# MCU-144pins.net
KiCad netlist of a schematic drawn in Altium Designer
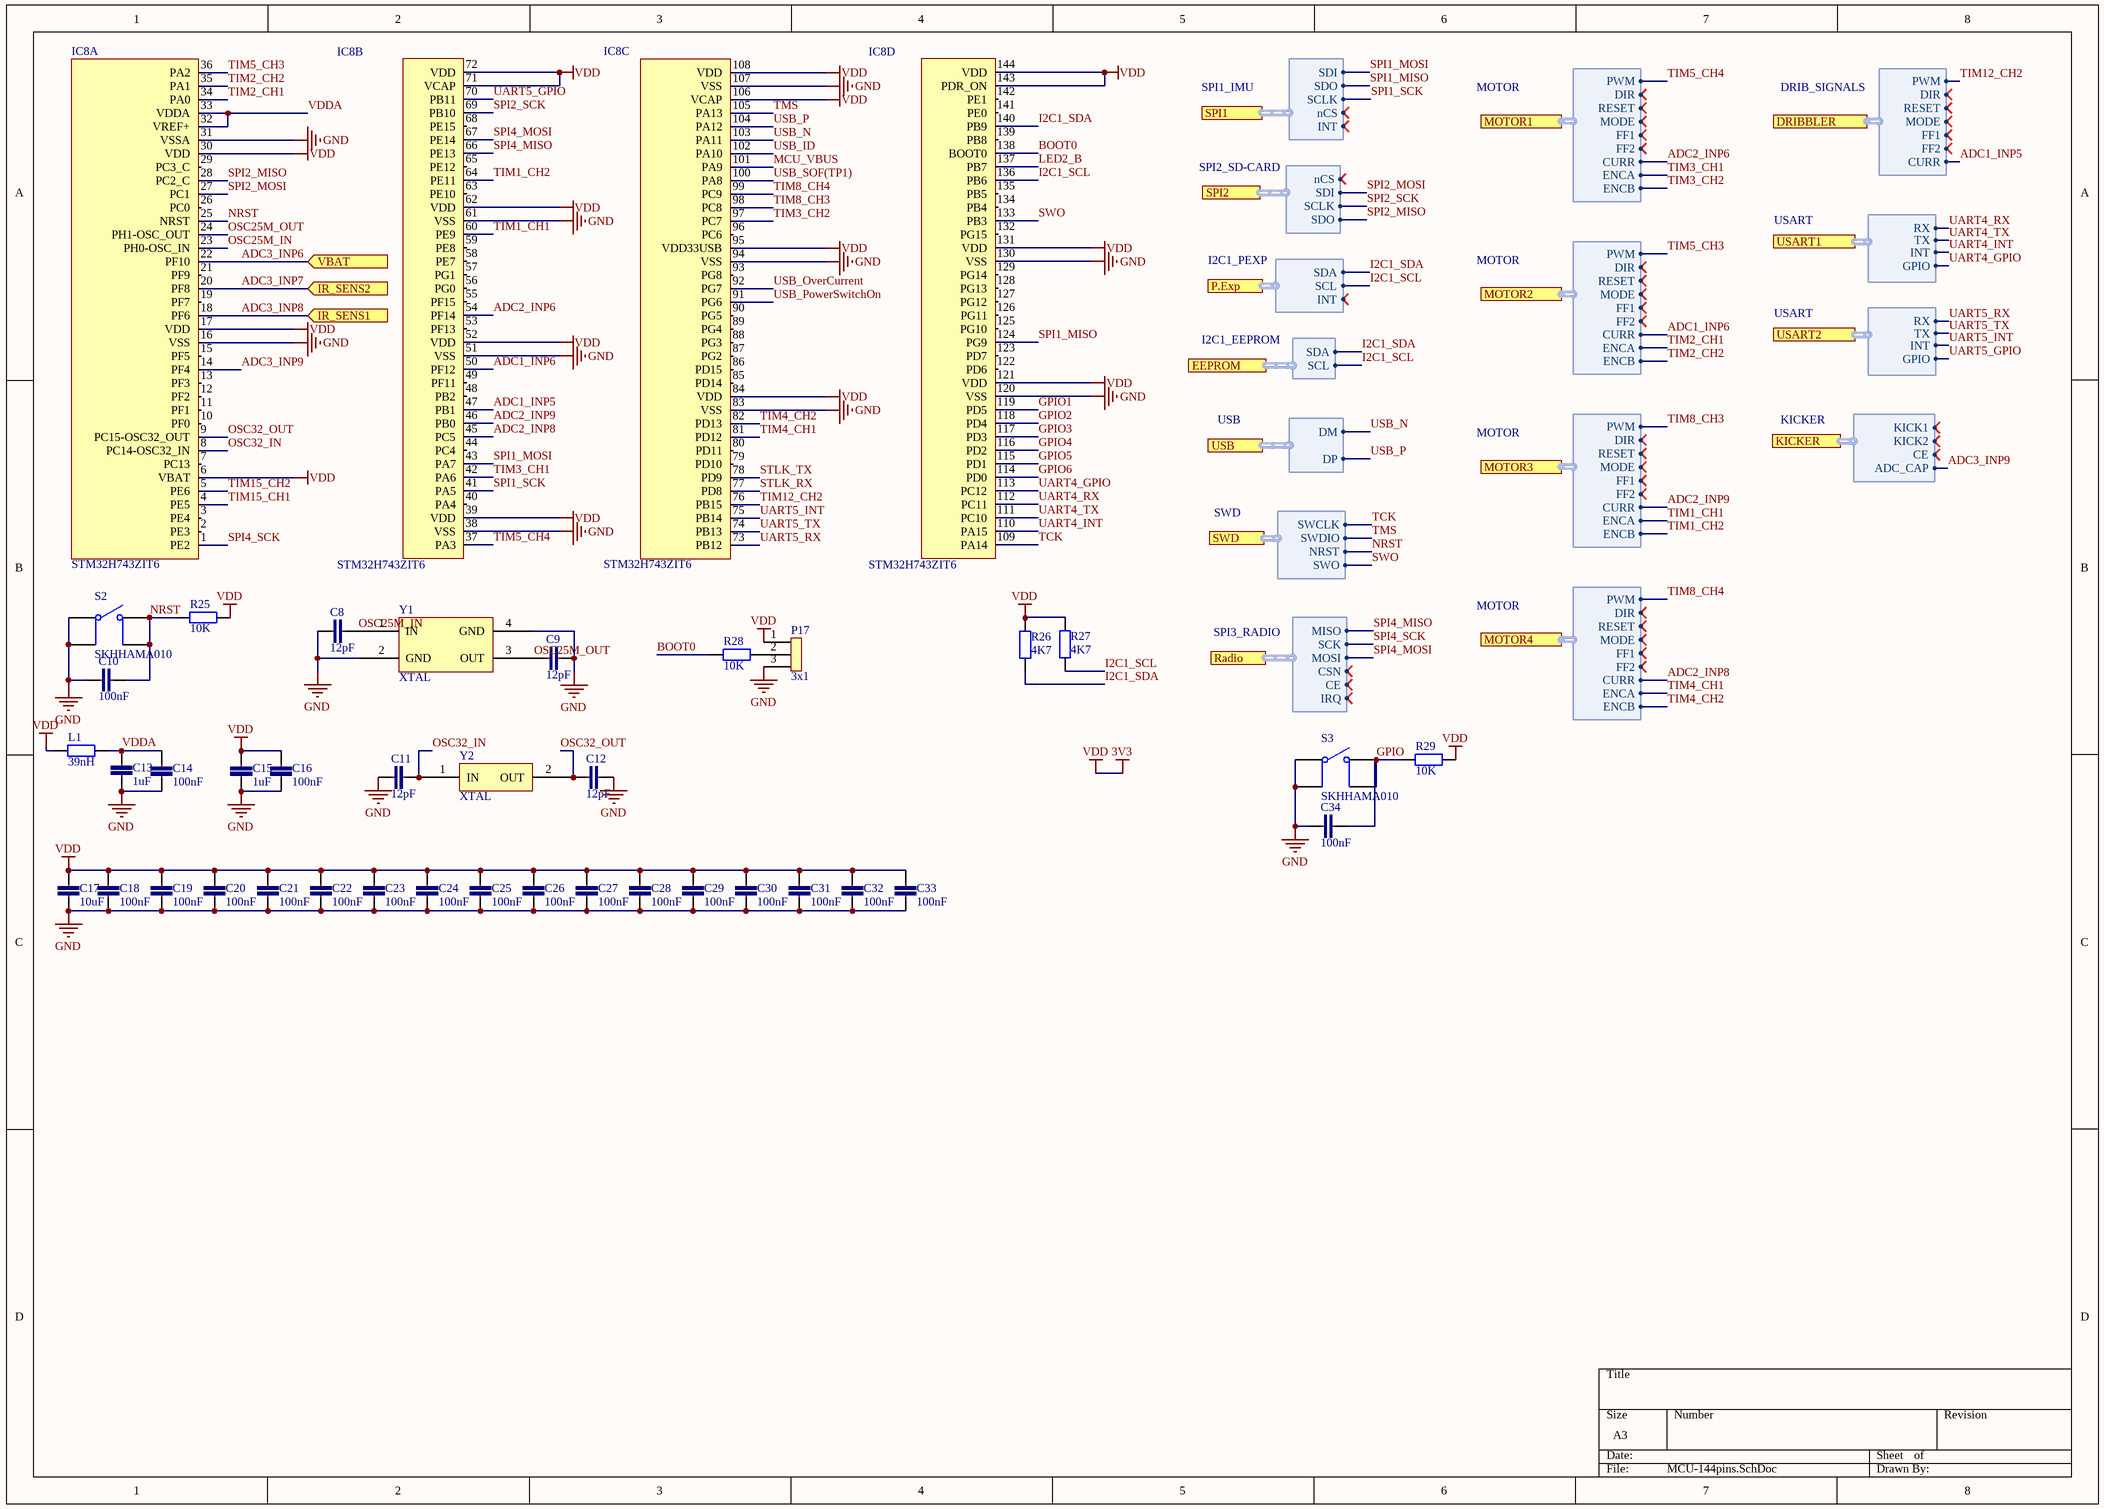
[diagram p0: MCU-144pins.SchDoc]

(export (version "E")
  (design (tool "Eeschema 10.0.6"))
  (components
    (comp (ref "C8")
      (value "12pF")
      (footprint "CAP CER 0603")
      (description "Multilayer Ceramic Capacitors MLCC - SMD/SMT 50V 12pF 0603 C0G 5%")
      (fields (field (name "MFR") "KEMET"))
      (libsource (lib "SSL-2020-SchLib1") (part "CAP CER 0603 50V 12pF"))
    )
    (comp (ref "C9")
      (value "12pF")
      (footprint "CAP CER 0603")
      (description "Multilayer Ceramic Capacitors MLCC - SMD/SMT 50V 12pF 0603 C0G 5%")
      (fields (field (name "MFR") "KEMET"))
      (libsource (lib "SSL-2020-SchLib1") (part "CAP CER 0603 50V 12pF"))
    )
    (comp (ref "C10")
      (value "100nF")
      (footprint "CAP CER 0603")
      (description "Multilayer Ceramic Capacitors MLCC - SMD/SMT 25V 0.1uF 0603 Y5V -20/+80%")
      (fields (field (name "MFR") "KEMET"))
      (libsource (lib "") (part "CAP CER 0603 25V 100nF_1"))
    )
    (comp (ref "C11")
      (value "12pF")
      (footprint "CAP CER 0603")
      (description "Multilayer Ceramic Capacitors MLCC - SMD/SMT 50V 12pF 0603 C0G 5%")
      (fields (field (name "MFR") "KEMET"))
      (libsource (lib "SSL-2020-SchLib1") (part "CAP CER 0603 50V 12pF"))
    )
    (comp (ref "C12")
      (value "12pF")
      (footprint "CAP CER 0603")
      (description "Multilayer Ceramic Capacitors MLCC - SMD/SMT 50V 12pF 0603 C0G 5%")
      (fields (field (name "MFR") "KEMET"))
      (libsource (lib "SSL-2020-SchLib1") (part "CAP CER 0603 50V 12pF"))
    )
    (comp (ref "C13")
      (value "1uF")
      (footprint "CAP CER 0603")
      (description "Multilayer Ceramic Capacitors MLCC - SMD/SMT 1uF 25V X5R 10%")
      (fields (field (name "MFR") "KEMET"))
      (libsource (lib "SSL-2020-SchLib1") (part "CAP CER 0603 25V 1uF"))
    )
    (comp (ref "C14")
      (value "100nF")
      (footprint "CAP CER 0603")
      (description "Multilayer Ceramic Capacitors MLCC - SMD/SMT 25V 0.1uF 0603 Y5V -20/+80%")
      (fields (field (name "MFR") "KEMET"))
      (libsource (lib "SSL-2020-SchLib1") (part "CAP CER 0603 25V 100nF"))
    )
    (comp (ref "C15")
      (value "1uF")
      (footprint "CAP CER 0603")
      (description "Multilayer Ceramic Capacitors MLCC - SMD/SMT 1uF 25V X5R 10%")
      (fields (field (name "MFR") "KEMET"))
      (libsource (lib "SSL-2020-SchLib1") (part "CAP CER 0603 25V 1uF"))
    )
    (comp (ref "C16")
      (value "100nF")
      (footprint "CAP CER 0603")
      (description "Multilayer Ceramic Capacitors MLCC - SMD/SMT 25V 0.1uF 0603 Y5V -20/+80%")
      (fields (field (name "MFR") "KEMET"))
      (libsource (lib "SSL-2020-SchLib1") (part "CAP CER 0603 25V 100nF"))
    )
    (comp (ref "C17")
      (value "10uF")
      (footprint "CAP CER 0603")
      (description "Multilayer Ceramic Capacitors MLCC - SMD/SMT 0603 6.3V 10uF X5R 10% Soft Term")
      (fields (field (name "MFR") "TDK"))
      (libsource (lib "SSL-2020-SchLib1") (part "CAP CER 0603 6.3V 10uF"))
    )
    (comp (ref "C18")
      (value "100nF")
      (footprint "CAP CER 0603")
      (description "Multilayer Ceramic Capacitors MLCC - SMD/SMT 25V 0.1uF 0603 Y5V -20/+80%")
      (fields (field (name "MFR") "KEMET"))
      (libsource (lib "SSL-2020-SchLib1") (part "CAP CER 0603 25V 100nF"))
    )
    (comp (ref "C19")
      (value "100nF")
      (footprint "CAP CER 0603")
      (description "Multilayer Ceramic Capacitors MLCC - SMD/SMT 25V 0.1uF 0603 Y5V -20/+80%")
      (fields (field (name "MFR") "KEMET"))
      (libsource (lib "SSL-2020-SchLib1") (part "CAP CER 0603 25V 100nF"))
    )
    (comp (ref "C20")
      (value "100nF")
      (footprint "CAP CER 0603")
      (description "Multilayer Ceramic Capacitors MLCC - SMD/SMT 25V 0.1uF 0603 Y5V -20/+80%")
      (fields (field (name "MFR") "KEMET"))
      (libsource (lib "SSL-2020-SchLib1") (part "CAP CER 0603 25V 100nF"))
    )
    (comp (ref "C21")
      (value "100nF")
      (footprint "CAP CER 0603")
      (description "Multilayer Ceramic Capacitors MLCC - SMD/SMT 25V 0.1uF 0603 Y5V -20/+80%")
      (fields (field (name "MFR") "KEMET"))
      (libsource (lib "SSL-2020-SchLib1") (part "CAP CER 0603 25V 100nF"))
    )
    (comp (ref "C22")
      (value "100nF")
      (footprint "CAP CER 0603")
      (description "Multilayer Ceramic Capacitors MLCC - SMD/SMT 25V 0.1uF 0603 Y5V -20/+80%")
      (fields (field (name "MFR") "KEMET"))
      (libsource (lib "SSL-2020-SchLib1") (part "CAP CER 0603 25V 100nF"))
    )
    (comp (ref "C23")
      (value "100nF")
      (footprint "CAP CER 0603")
      (description "Multilayer Ceramic Capacitors MLCC - SMD/SMT 25V 0.1uF 0603 Y5V -20/+80%")
      (fields (field (name "MFR") "KEMET"))
      (libsource (lib "SSL-2020-SchLib1") (part "CAP CER 0603 25V 100nF"))
    )
    (comp (ref "C24")
      (value "100nF")
      (footprint "CAP CER 0603")
      (description "Multilayer Ceramic Capacitors MLCC - SMD/SMT 25V 0.1uF 0603 Y5V -20/+80%")
      (fields (field (name "MFR") "KEMET"))
      (libsource (lib "SSL-2020-SchLib1") (part "CAP CER 0603 25V 100nF"))
    )
    (comp (ref "C25")
      (value "100nF")
      (footprint "CAP CER 0603")
      (description "Multilayer Ceramic Capacitors MLCC - SMD/SMT 25V 0.1uF 0603 Y5V -20/+80%")
      (fields (field (name "MFR") "KEMET"))
      (libsource (lib "SSL-2020-SchLib1") (part "CAP CER 0603 25V 100nF"))
    )
    (comp (ref "C26")
      (value "100nF")
      (footprint "CAP CER 0603")
      (description "Multilayer Ceramic Capacitors MLCC - SMD/SMT 25V 0.1uF 0603 Y5V -20/+80%")
      (fields (field (name "MFR") "KEMET"))
      (libsource (lib "SSL-2020-SchLib1") (part "CAP CER 0603 25V 100nF"))
    )
    (comp (ref "C27")
      (value "100nF")
      (footprint "CAP CER 0603")
      (description "Multilayer Ceramic Capacitors MLCC - SMD/SMT 25V 0.1uF 0603 Y5V -20/+80%")
      (fields (field (name "MFR") "KEMET"))
      (libsource (lib "SSL-2020-SchLib1") (part "CAP CER 0603 25V 100nF"))
    )
    (comp (ref "C28")
      (value "100nF")
      (footprint "CAP CER 0603")
      (description "Multilayer Ceramic Capacitors MLCC - SMD/SMT 25V 0.1uF 0603 Y5V -20/+80%")
      (fields (field (name "MFR") "KEMET"))
      (libsource (lib "SSL-2020-SchLib1") (part "CAP CER 0603 25V 100nF"))
    )
    (comp (ref "C29")
      (value "100nF")
      (footprint "CAP CER 0603")
      (description "Multilayer Ceramic Capacitors MLCC - SMD/SMT 25V 0.1uF 0603 Y5V -20/+80%")
      (fields (field (name "MFR") "KEMET"))
      (libsource (lib "SSL-2020-SchLib1") (part "CAP CER 0603 25V 100nF"))
    )
    (comp (ref "C30")
      (value "100nF")
      (footprint "CAP CER 0603")
      (description "Multilayer Ceramic Capacitors MLCC - SMD/SMT 25V 0.1uF 0603 Y5V -20/+80%")
      (fields (field (name "MFR") "KEMET"))
      (libsource (lib "SSL-2020-SchLib1") (part "CAP CER 0603 25V 100nF"))
    )
    (comp (ref "C31")
      (value "100nF")
      (footprint "CAP CER 0603")
      (description "Multilayer Ceramic Capacitors MLCC - SMD/SMT 25V 0.1uF 0603 Y5V -20/+80%")
      (fields (field (name "MFR") "KEMET"))
      (libsource (lib "SSL-2020-SchLib1") (part "CAP CER 0603 25V 100nF"))
    )
    (comp (ref "C32")
      (value "100nF")
      (footprint "CAP CER 0603")
      (description "Multilayer Ceramic Capacitors MLCC - SMD/SMT 25V 0.1uF 0603 Y5V -20/+80%")
      (fields (field (name "MFR") "KEMET"))
      (libsource (lib "SSL-2020-SchLib1") (part "CAP CER 0603 25V 100nF"))
    )
    (comp (ref "C33")
      (value "100nF")
      (footprint "CAP CER 0603")
      (description "Multilayer Ceramic Capacitors MLCC - SMD/SMT 25V 0.1uF 0603 Y5V -20/+80%")
      (fields (field (name "MFR") "KEMET"))
      (libsource (lib "SSL-2020-SchLib1") (part "CAP CER 0603 25V 100nF"))
    )
    (comp (ref "C34")
      (value "100nF")
      (footprint "CAP CER 0603")
      (description "Multilayer Ceramic Capacitors MLCC - SMD/SMT 25V 0.1uF 0603 Y5V -20/+80%")
      (fields (field (name "MFR") "KEMET"))
      (libsource (lib "") (part "CAP CER 0603 25V 100nF_1"))
    )
    (comp (ref "IC8")
      (value "STM32H743ZIT6")
      (footprint "LQFP-144")
      (fields (field (name "MFR") "STMicroelectronics"))
      (libsource (lib "SSL-2020-SchLib1") (part "STM32H743ZIT6"))
    )
    (comp (ref "L1")
      (value "39nH")
      (footprint "IND SMD 0603")
      (description "FIXED IND 39NH 300MA 600 MOHM")
      (libsource (lib "SSL-2020-SchLib1") (part "IND SMD 0603 300mA"))
    )
    (comp (ref "P17")
      (value "3x1")
      (footprint "HEADER 3X1 MALE")
      (description "Headers & Wire Housings 03 SIL VERTICAL PIN HEADER TIN")
      (libsource (lib "SSL-2020-SchLib1") (part "HEADER 3P M"))
    )
    (comp (ref "R25")
      (value "10K")
      (footprint "RES SMD 0603")
      (description "Thick Film Resistors - SMD 1/10Watt 10Kohms 1% Commercial Use")
      (fields (field (name "MFR") "Vishay / Dale"))
      (libsource (lib "SSL-2020-SchLib1") (part "RES SMD 0603 10K"))
    )
    (comp (ref "R26")
      (value "4K7")
      (footprint "RES SMD 0603")
      (libsource (lib "SSL-2020-SchLib1") (part "RES SMD 0603 4K7"))
    )
    (comp (ref "R27")
      (value "4K7")
      (footprint "RES SMD 0603")
      (libsource (lib "SSL-2020-SchLib1") (part "RES SMD 0603 4K7"))
    )
    (comp (ref "R28")
      (value "10K")
      (footprint "RES SMD 0603")
      (description "Thick Film Resistors - SMD 1/10Watt 10Kohms 1% Commercial Use")
      (fields (field (name "MFR") "Vishay / Dale"))
      (libsource (lib "SSL-2020-SchLib1") (part "RES SMD 0603 10K"))
    )
    (comp (ref "R29")
      (value "10K")
      (footprint "RES SMD 0603")
      (description "Thick Film Resistors - SMD 1/10Watt 10Kohms 1% Commercial Use")
      (fields (field (name "MFR") "Vishay / Dale"))
      (libsource (lib "SSL-2020-SchLib1") (part "RES SMD 0603 10K"))
    )
    (comp (ref "S2")
      (value "SKHHAMA010")
      (footprint "TACT-SWITCH-6X6X5")
      (description "Tactile Switches 6.0x6.0x5.0mm 160gf")
      (fields (field (name "MFR") "ALPS"))
      (libsource (lib "SSL-2020-SchLib1") (part "SKHHAMA010"))
    )
    (comp (ref "S3")
      (value "SKHHAMA010")
      (footprint "TACT-SWITCH-6X6X5")
      (description "Tactile Switches 6.0x6.0x5.0mm 160gf")
      (fields (field (name "MFR") "ALPS"))
      (libsource (lib "SSL-2020-SchLib1") (part "SKHHAMA010"))
    )
    (comp (ref "Y1")
      (value "XTAL")
      (footprint "XTAL-200X160")
      (description "Crystals 25MHz 10PPM -20C +75C 9.0pF")
      (fields (field (name "MFR") "Epson Timing") (field (name "TOLERANCE") "10 PPM"))
      (libsource (lib "SSL-2020-SchLib1") (part "FA-12825F10Z-AC"))
    )
    (comp (ref "Y2")
      (value "XTAL")
      (footprint "XTAL-200X120")
      (description "Crystals 32.768KHz 9pF 20ppm -40 C+85C")
      (fields (field (name "MFR") "ABRACON") (field (name "TOLERANCE") "20 PPM"))
      (libsource (lib "SSL-2020-SchLib1") (part "ABS06-32.768KHZ-9-T"))
    )
  )
  (nets
    (net (code "12") (name "/ADC1_INP5") (class "Default")
      (node (ref "IC8") (pin "47") (pinfunction "PB1_47") (pintype "passive"))
    )
    (net (code "13") (name "/ADC1_INP6") (class "Default")
      (node (ref "IC8") (pin "50") (pinfunction "PF12_50") (pintype "passive"))
    )
    (net (code "14") (name "/ADC2_INP6") (class "Default")
      (node (ref "IC8") (pin "54") (pinfunction "PF14_54") (pintype "passive"))
    )
    (net (code "15") (name "/ADC2_INP8") (class "Default")
      (node (ref "IC8") (pin "45") (pinfunction "PC5_45") (pintype "passive"))
    )
    (net (code "16") (name "/ADC2_INP9") (class "Default")
      (node (ref "IC8") (pin "46") (pinfunction "PB0_46") (pintype "passive"))
    )
    (net (code "17") (name "/ADC3_INP6") (class "Default")
      (node (ref "IC8") (pin "22") (pinfunction "PF10_22") (pintype "passive"))
    )
    (net (code "18") (name "/ADC3_INP7") (class "Default")
      (node (ref "IC8") (pin "20") (pinfunction "PF8_20") (pintype "passive"))
    )
    (net (code "19") (name "/ADC3_INP8") (class "Default")
      (node (ref "IC8") (pin "18") (pinfunction "PF6_18") (pintype "passive"))
    )
    (net (code "20") (name "/ADC3_INP9") (class "Default")
      (node (ref "IC8") (pin "14") (pinfunction "PF4_14") (pintype "passive"))
    )
    (net (code "21") (name "/BOOT0") (class "Default")
      (node (ref "IC8") (pin "138") (pinfunction "BOOT0_138") (pintype "passive"))
      (node (ref "R28") (pin "2") (pinfunction "2_2") (pintype "passive"))
    )
    (net (code "22") (name "/GPIO") (class "Default")
      (node (ref "C34") (pin "2") (pinfunction "2_2") (pintype "passive"))
      (node (ref "R29") (pin "2") (pinfunction "2_2") (pintype "passive"))
      (node (ref "S3") (pin "3") (pinfunction "3_3") (pintype "passive"))
      (node (ref "S3") (pin "4") (pinfunction "4_4") (pintype "passive"))
    )
    (net (code "23") (name "/GPIO1") (class "Default")
      (node (ref "IC8") (pin "119") (pinfunction "PD5_119") (pintype "passive"))
    )
    (net (code "24") (name "/GPIO2") (class "Default")
      (node (ref "IC8") (pin "118") (pinfunction "PD4_118") (pintype "passive"))
    )
    (net (code "25") (name "/GPIO3") (class "Default")
      (node (ref "IC8") (pin "117") (pinfunction "PD3_117") (pintype "passive"))
    )
    (net (code "26") (name "/GPIO4") (class "Default")
      (node (ref "IC8") (pin "116") (pinfunction "PD2_116") (pintype "passive"))
    )
    (net (code "27") (name "/GPIO5") (class "Default")
      (node (ref "IC8") (pin "115") (pinfunction "PD1_115") (pintype "passive"))
    )
    (net (code "28") (name "/GPIO6") (class "Default")
      (node (ref "IC8") (pin "114") (pinfunction "PD0_114") (pintype "passive"))
    )
    (net (code "29") (name "/I2C1_SCL") (class "Default")
      (node (ref "IC8") (pin "136") (pinfunction "PB6_136") (pintype "passive"))
      (node (ref "R27") (pin "1") (pinfunction "1_1") (pintype "passive"))
    )
    (net (code "30") (name "/I2C1_SDA") (class "Default")
      (node (ref "IC8") (pin "140") (pinfunction "PB9_140") (pintype "passive"))
      (node (ref "R26") (pin "1") (pinfunction "1_1") (pintype "passive"))
    )
    (net (code "31") (name "/LED2_B") (class "Default")
      (node (ref "IC8") (pin "137") (pinfunction "PB7_137") (pintype "passive"))
    )
    (net (code "32") (name "/MCU_VBUS") (class "Default")
      (node (ref "IC8") (pin "101") (pinfunction "PA9_101") (pintype "passive"))
    )
    (net (code "33") (name "/NRST") (class "Default")
      (node (ref "C10") (pin "2") (pinfunction "2_2") (pintype "passive"))
      (node (ref "IC8") (pin "25") (pinfunction "NRST_25") (pintype "passive"))
      (node (ref "R25") (pin "2") (pinfunction "2_2") (pintype "passive"))
      (node (ref "S2") (pin "3") (pinfunction "3_3") (pintype "passive"))
      (node (ref "S2") (pin "4") (pinfunction "4_4") (pintype "passive"))
    )
    (net (code "34") (name "/OSC25M_IN") (class "Default")
      (node (ref "C8") (pin "2") (pinfunction "2_2") (pintype "passive"))
      (node (ref "IC8") (pin "23") (pinfunction "PH0-OSC_IN_23") (pintype "passive"))
      (node (ref "Y1") (pin "1") (pinfunction "IN_1") (pintype "passive"))
    )
    (net (code "35") (name "/OSC25M_OUT") (class "Default")
      (node (ref "C9") (pin "1") (pinfunction "1_1") (pintype "passive"))
      (node (ref "IC8") (pin "24") (pinfunction "PH1-OSC_OUT_24") (pintype "passive"))
      (node (ref "Y1") (pin "3") (pinfunction "OUT_3") (pintype "passive"))
    )
    (net (code "36") (name "/OSC32_IN") (class "Default")
      (node (ref "C11") (pin "2") (pinfunction "2_2") (pintype "passive"))
      (node (ref "IC8") (pin "8") (pinfunction "PC14-OSC32_IN_8") (pintype "passive"))
      (node (ref "Y2") (pin "1") (pinfunction "IN_1") (pintype "passive"))
    )
    (net (code "37") (name "/OSC32_OUT") (class "Default")
      (node (ref "C12") (pin "1") (pinfunction "1_1") (pintype "passive"))
      (node (ref "IC8") (pin "9") (pinfunction "PC15-OSC32_OUT_9") (pintype "passive"))
      (node (ref "Y2") (pin "2") (pinfunction "OUT_2") (pintype "passive"))
    )
    (net (code "38") (name "/SPI1_MISO") (class "Default")
      (node (ref "IC8") (pin "124") (pinfunction "PG9_124") (pintype "passive"))
    )
    (net (code "39") (name "/SPI1_MOSI") (class "Default")
      (node (ref "IC8") (pin "43") (pinfunction "PA7_43") (pintype "passive"))
    )
    (net (code "40") (name "/SPI1_SCK") (class "Default")
      (node (ref "IC8") (pin "41") (pinfunction "PA5_41") (pintype "passive"))
    )
    (net (code "41") (name "/SPI2_MISO") (class "Default")
      (node (ref "IC8") (pin "28") (pinfunction "PC2_C_28") (pintype "passive"))
    )
    (net (code "42") (name "/SPI2_MOSI") (class "Default")
      (node (ref "IC8") (pin "27") (pinfunction "PC1_27") (pintype "passive"))
    )
    (net (code "43") (name "/SPI2_SCK") (class "Default")
      (node (ref "IC8") (pin "69") (pinfunction "PB10_69") (pintype "passive"))
    )
    (net (code "44") (name "/SPI4_MISO") (class "Default")
      (node (ref "IC8") (pin "66") (pinfunction "PE13_66") (pintype "passive"))
    )
    (net (code "45") (name "/SPI4_MOSI") (class "Default")
      (node (ref "IC8") (pin "67") (pinfunction "PE14_67") (pintype "passive"))
    )
    (net (code "46") (name "/SPI4_SCK") (class "Default")
      (node (ref "IC8") (pin "1") (pinfunction "PE2_1") (pintype "passive"))
    )
    (net (code "47") (name "/STLK_RX") (class "Default")
      (node (ref "IC8") (pin "77") (pinfunction "PD8_77") (pintype "passive"))
    )
    (net (code "48") (name "/STLK_TX") (class "Default")
      (node (ref "IC8") (pin "78") (pinfunction "PD9_78") (pintype "passive"))
    )
    (net (code "49") (name "/SWO") (class "Default")
      (node (ref "IC8") (pin "133") (pinfunction "PB3_133") (pintype "passive"))
    )
    (net (code "50") (name "/TCK") (class "Default")
      (node (ref "IC8") (pin "109") (pinfunction "PA14_109") (pintype "passive"))
    )
    (net (code "51") (name "/TIM1_CH1") (class "Default")
      (node (ref "IC8") (pin "60") (pinfunction "PE9_60") (pintype "passive"))
    )
    (net (code "52") (name "/TIM1_CH2") (class "Default")
      (node (ref "IC8") (pin "64") (pinfunction "PE11_64") (pintype "passive"))
    )
    (net (code "53") (name "/TIM2_CH1") (class "Default")
      (node (ref "IC8") (pin "34") (pinfunction "PA0_34") (pintype "passive"))
    )
    (net (code "54") (name "/TIM2_CH2") (class "Default")
      (node (ref "IC8") (pin "35") (pinfunction "PA1_35") (pintype "passive"))
    )
    (net (code "55") (name "/TIM3_CH1") (class "Default")
      (node (ref "IC8") (pin "42") (pinfunction "PA6_42") (pintype "passive"))
    )
    (net (code "56") (name "/TIM3_CH2") (class "Default")
      (node (ref "IC8") (pin "97") (pinfunction "PC7_97") (pintype "passive"))
    )
    (net (code "57") (name "/TIM4_CH1") (class "Default")
      (node (ref "IC8") (pin "81") (pinfunction "PD12_81") (pintype "passive"))
    )
    (net (code "58") (name "/TIM4_CH2") (class "Default")
      (node (ref "IC8") (pin "82") (pinfunction "PD13_82") (pintype "passive"))
    )
    (net (code "59") (name "/TIM5_CH3") (class "Default")
      (node (ref "IC8") (pin "36") (pinfunction "PA2_36") (pintype "passive"))
    )
    (net (code "60") (name "/TIM5_CH4") (class "Default")
      (node (ref "IC8") (pin "37") (pinfunction "PA3_37") (pintype "passive"))
    )
    (net (code "61") (name "/TIM8_CH3") (class "Default")
      (node (ref "IC8") (pin "98") (pinfunction "PC8_98") (pintype "passive"))
    )
    (net (code "62") (name "/TIM8_CH4") (class "Default")
      (node (ref "IC8") (pin "99") (pinfunction "PC9_99") (pintype "passive"))
    )
    (net (code "63") (name "/TIM12_CH2") (class "Default")
      (node (ref "IC8") (pin "76") (pinfunction "PB15_76") (pintype "passive"))
    )
    (net (code "64") (name "/TIM15_CH1") (class "Default")
      (node (ref "IC8") (pin "4") (pinfunction "PE5_4") (pintype "passive"))
    )
    (net (code "65") (name "/TIM15_CH2") (class "Default")
      (node (ref "IC8") (pin "5") (pinfunction "PE6_5") (pintype "passive"))
    )
    (net (code "66") (name "/TMS") (class "Default")
      (node (ref "IC8") (pin "105") (pinfunction "PA13_105") (pintype "passive"))
    )
    (net (code "67") (name "/UART4_GPIO") (class "Default")
      (node (ref "IC8") (pin "113") (pinfunction "PC12_113") (pintype "passive"))
    )
    (net (code "68") (name "/UART4_INT") (class "Default")
      (node (ref "IC8") (pin "110") (pinfunction "PA15_110") (pintype "passive"))
    )
    (net (code "69") (name "/UART4_RX") (class "Default")
      (node (ref "IC8") (pin "112") (pinfunction "PC11_112") (pintype "passive"))
    )
    (net (code "70") (name "/UART4_TX") (class "Default")
      (node (ref "IC8") (pin "111") (pinfunction "PC10_111") (pintype "passive"))
    )
    (net (code "71") (name "/UART5_GPIO") (class "Default")
      (node (ref "IC8") (pin "70") (pinfunction "PB11_70") (pintype "passive"))
    )
    (net (code "72") (name "/UART5_INT") (class "Default")
      (node (ref "IC8") (pin "75") (pinfunction "PB14_75") (pintype "passive"))
    )
    (net (code "73") (name "/UART5_RX") (class "Default")
      (node (ref "IC8") (pin "73") (pinfunction "PB12_73") (pintype "passive"))
    )
    (net (code "74") (name "/UART5_TX") (class "Default")
      (node (ref "IC8") (pin "74") (pinfunction "PB13_74") (pintype "passive"))
    )
    (net (code "75") (name "/USB_ID") (class "Default")
      (node (ref "IC8") (pin "102") (pinfunction "PA10_102") (pintype "passive"))
    )
    (net (code "76") (name "/USB_N") (class "Default")
      (node (ref "IC8") (pin "103") (pinfunction "PA11_103") (pintype "passive"))
    )
    (net (code "77") (name "/USB_OverCurrent") (class "Default")
      (node (ref "IC8") (pin "92") (pinfunction "PG7_92") (pintype "passive"))
    )
    (net (code "78") (name "/USB_P") (class "Default")
      (node (ref "IC8") (pin "104") (pinfunction "PA12_104") (pintype "passive"))
    )
    (net (code "79") (name "/USB_PowerSwitchOn") (class "Default")
      (node (ref "IC8") (pin "91") (pinfunction "PG6_91") (pintype "passive"))
    )
    (net (code "80") (name "/USB_SOF(TP1)") (class "Default")
      (node (ref "IC8") (pin "100") (pinfunction "PA8_100") (pintype "passive"))
    )
    (net (code "81") (name "/VDDA") (class "Default")
      (node (ref "C13") (pin "1") (pinfunction "1_1") (pintype "passive"))
      (node (ref "C14") (pin "1") (pinfunction "1_1") (pintype "passive"))
      (node (ref "IC8") (pin "32") (pinfunction "VREF+_32") (pintype "passive"))
      (node (ref "IC8") (pin "33") (pinfunction "VDDA_33") (pintype "passive"))
      (node (ref "L1") (pin "1") (pinfunction "1_1") (pintype "passive"))
    )
    (net (code "93") (name "3V3") (class "Default")
      (node (ref "C15") (pin "1") (pinfunction "1_1") (pintype "passive"))
      (node (ref "C16") (pin "1") (pinfunction "1_1") (pintype "passive"))
      (node (ref "C17") (pin "1") (pinfunction "1_1") (pintype "passive"))
      (node (ref "C18") (pin "1") (pinfunction "1_1") (pintype "passive"))
      (node (ref "C19") (pin "1") (pinfunction "1_1") (pintype "passive"))
      (node (ref "C20") (pin "1") (pinfunction "1_1") (pintype "passive"))
      (node (ref "C21") (pin "1") (pinfunction "1_1") (pintype "passive"))
      (node (ref "C22") (pin "1") (pinfunction "1_1") (pintype "passive"))
      (node (ref "C23") (pin "1") (pinfunction "1_1") (pintype "passive"))
      (node (ref "C24") (pin "1") (pinfunction "1_1") (pintype "passive"))
      (node (ref "C25") (pin "1") (pinfunction "1_1") (pintype "passive"))
      (node (ref "C26") (pin "1") (pinfunction "1_1") (pintype "passive"))
      (node (ref "C27") (pin "1") (pinfunction "1_1") (pintype "passive"))
      (node (ref "C28") (pin "1") (pinfunction "1_1") (pintype "passive"))
      (node (ref "C29") (pin "1") (pinfunction "1_1") (pintype "passive"))
      (node (ref "C30") (pin "1") (pinfunction "1_1") (pintype "passive"))
      (node (ref "C31") (pin "1") (pinfunction "1_1") (pintype "passive"))
      (node (ref "C32") (pin "1") (pinfunction "1_1") (pintype "passive"))
      (node (ref "C33") (pin "1") (pinfunction "1_1") (pintype "passive"))
      (node (ref "IC8") (pin "106") (pinfunction "VCAP_106") (pintype "passive"))
      (node (ref "IC8") (pin "108") (pinfunction "VDD_108") (pintype "passive"))
      (node (ref "IC8") (pin "121") (pinfunction "VDD_121") (pintype "passive"))
      (node (ref "IC8") (pin "131") (pinfunction "VDD_131") (pintype "passive"))
      (node (ref "IC8") (pin "143") (pinfunction "PDR_ON_143") (pintype "passive"))
      (node (ref "IC8") (pin "144") (pinfunction "VDD_144") (pintype "passive"))
      (node (ref "IC8") (pin "17") (pinfunction "VDD_17") (pintype "passive"))
      (node (ref "IC8") (pin "30") (pinfunction "VDD_30") (pintype "passive"))
      (node (ref "IC8") (pin "39") (pinfunction "VDD_39") (pintype "passive"))
      (node (ref "IC8") (pin "52") (pinfunction "VDD_52") (pintype "passive"))
      (node (ref "IC8") (pin "6") (pinfunction "VBAT_6") (pintype "passive"))
      (node (ref "IC8") (pin "62") (pinfunction "VDD_62") (pintype "passive"))
      (node (ref "IC8") (pin "71") (pinfunction "VCAP_71") (pintype "passive"))
      (node (ref "IC8") (pin "72") (pinfunction "VDD_72") (pintype "passive"))
      (node (ref "IC8") (pin "84") (pinfunction "VDD_84") (pintype "passive"))
      (node (ref "IC8") (pin "95") (pinfunction "VDD33USB_95") (pintype "passive"))
      (node (ref "L1") (pin "2") (pinfunction "2_2") (pintype "passive"))
      (node (ref "P17") (pin "1") (pinfunction "1_1") (pintype "passive"))
      (node (ref "R25") (pin "1") (pinfunction "1_1") (pintype "passive"))
      (node (ref "R26") (pin "2") (pinfunction "2_2") (pintype "passive"))
      (node (ref "R27") (pin "2") (pinfunction "2_2") (pintype "passive"))
      (node (ref "R29") (pin "1") (pinfunction "1_1") (pintype "passive"))
    )
    (net (code "94") (name "GND") (class "Default")
      (node (ref "C10") (pin "1") (pinfunction "1_1") (pintype "passive"))
      (node (ref "C11") (pin "1") (pinfunction "1_1") (pintype "passive"))
      (node (ref "C12") (pin "2") (pinfunction "2_2") (pintype "passive"))
      (node (ref "C13") (pin "2") (pinfunction "2_2") (pintype "passive"))
      (node (ref "C14") (pin "2") (pinfunction "2_2") (pintype "passive"))
      (node (ref "C15") (pin "2") (pinfunction "2_2") (pintype "passive"))
      (node (ref "C16") (pin "2") (pinfunction "2_2") (pintype "passive"))
      (node (ref "C17") (pin "2") (pinfunction "2_2") (pintype "passive"))
      (node (ref "C18") (pin "2") (pinfunction "2_2") (pintype "passive"))
      (node (ref "C19") (pin "2") (pinfunction "2_2") (pintype "passive"))
      (node (ref "C20") (pin "2") (pinfunction "2_2") (pintype "passive"))
      (node (ref "C21") (pin "2") (pinfunction "2_2") (pintype "passive"))
      (node (ref "C22") (pin "2") (pinfunction "2_2") (pintype "passive"))
      (node (ref "C23") (pin "2") (pinfunction "2_2") (pintype "passive"))
      (node (ref "C24") (pin "2") (pinfunction "2_2") (pintype "passive"))
      (node (ref "C25") (pin "2") (pinfunction "2_2") (pintype "passive"))
      (node (ref "C26") (pin "2") (pinfunction "2_2") (pintype "passive"))
      (node (ref "C27") (pin "2") (pinfunction "2_2") (pintype "passive"))
      (node (ref "C28") (pin "2") (pinfunction "2_2") (pintype "passive"))
      (node (ref "C29") (pin "2") (pinfunction "2_2") (pintype "passive"))
      (node (ref "C30") (pin "2") (pinfunction "2_2") (pintype "passive"))
      (node (ref "C31") (pin "2") (pinfunction "2_2") (pintype "passive"))
      (node (ref "C32") (pin "2") (pinfunction "2_2") (pintype "passive"))
      (node (ref "C33") (pin "2") (pinfunction "2_2") (pintype "passive"))
      (node (ref "C34") (pin "1") (pinfunction "1_1") (pintype "passive"))
      (node (ref "C8") (pin "1") (pinfunction "1_1") (pintype "passive"))
      (node (ref "C9") (pin "2") (pinfunction "2_2") (pintype "passive"))
      (node (ref "IC8") (pin "107") (pinfunction "VSS_107") (pintype "passive"))
      (node (ref "IC8") (pin "120") (pinfunction "VSS_120") (pintype "passive"))
      (node (ref "IC8") (pin "130") (pinfunction "VSS_130") (pintype "passive"))
      (node (ref "IC8") (pin "16") (pinfunction "VSS_16") (pintype "passive"))
      (node (ref "IC8") (pin "31") (pinfunction "VSSA_31") (pintype "passive"))
      (node (ref "IC8") (pin "38") (pinfunction "VSS_38") (pintype "passive"))
      (node (ref "IC8") (pin "51") (pinfunction "VSS_51") (pintype "passive"))
      (node (ref "IC8") (pin "61") (pinfunction "VSS_61") (pintype "passive"))
      (node (ref "IC8") (pin "83") (pinfunction "VSS_83") (pintype "passive"))
      (node (ref "IC8") (pin "94") (pinfunction "VSS_94") (pintype "passive"))
      (node (ref "P17") (pin "3") (pinfunction "3_3") (pintype "passive"))
      (node (ref "S2") (pin "1") (pinfunction "1_1") (pintype "passive"))
      (node (ref "S2") (pin "2") (pinfunction "2_2") (pintype "passive"))
      (node (ref "S3") (pin "1") (pinfunction "1_1") (pintype "passive"))
      (node (ref "S3") (pin "2") (pinfunction "2_2") (pintype "passive"))
      (node (ref "Y1") (pin "2") (pinfunction "GND_2") (pintype "passive"))
      (node (ref "Y1") (pin "4") (pinfunction "GND_4") (pintype "passive"))
    )
    (net (code "95") (name "Net-(P17-Pad2)") (class "Default")
      (node (ref "P17") (pin "2") (pinfunction "2_2") (pintype "passive"))
      (node (ref "R28") (pin "1") (pinfunction "1_1") (pintype "passive"))
    )
    (net (code "96") (name "unconnected-(IC8A-PC0-Pad26)") (class "Default")
      (node (ref "IC8") (pin "26") (pinfunction "PC0_26") (pintype "passive"))
    )
    (net (code "97") (name "unconnected-(IC8A-PC3_C-Pad29)") (class "Default")
      (node (ref "IC8") (pin "29") (pinfunction "PC3_C_29") (pintype "passive"))
    )
    (net (code "98") (name "unconnected-(IC8A-PC13-Pad7)") (class "Default")
      (node (ref "IC8") (pin "7") (pinfunction "PC13_7") (pintype "passive"))
    )
    (net (code "99") (name "unconnected-(IC8A-PE3-Pad2)") (class "Default")
      (node (ref "IC8") (pin "2") (pinfunction "PE3_2") (pintype "passive"))
    )
    (net (code "100") (name "unconnected-(IC8A-PE4-Pad3)") (class "Default")
      (node (ref "IC8") (pin "3") (pinfunction "PE4_3") (pintype "passive"))
    )
    (net (code "101") (name "unconnected-(IC8A-PF0-Pad10)") (class "Default")
      (node (ref "IC8") (pin "10") (pinfunction "PF0_10") (pintype "passive"))
    )
    (net (code "102") (name "unconnected-(IC8A-PF1-Pad11)") (class "Default")
      (node (ref "IC8") (pin "11") (pinfunction "PF1_11") (pintype "passive"))
    )
    (net (code "103") (name "unconnected-(IC8A-PF2-Pad12)") (class "Default")
      (node (ref "IC8") (pin "12") (pinfunction "PF2_12") (pintype "passive"))
    )
    (net (code "104") (name "unconnected-(IC8A-PF3-Pad13)") (class "Default")
      (node (ref "IC8") (pin "13") (pinfunction "PF3_13") (pintype "passive"))
    )
    (net (code "105") (name "unconnected-(IC8A-PF5-Pad15)") (class "Default")
      (node (ref "IC8") (pin "15") (pinfunction "PF5_15") (pintype "passive"))
    )
    (net (code "106") (name "unconnected-(IC8A-PF7-Pad19)") (class "Default")
      (node (ref "IC8") (pin "19") (pinfunction "PF7_19") (pintype "passive"))
    )
    (net (code "107") (name "unconnected-(IC8A-PF9-Pad21)") (class "Default")
      (node (ref "IC8") (pin "21") (pinfunction "PF9_21") (pintype "passive"))
    )
    (net (code "108") (name "unconnected-(IC8B-PA4-Pad40)") (class "Default")
      (node (ref "IC8") (pin "40") (pinfunction "PA4_40") (pintype "passive"))
    )
    (net (code "109") (name "unconnected-(IC8B-PB2-Pad48)") (class "Default")
      (node (ref "IC8") (pin "48") (pinfunction "PB2_48") (pintype "passive"))
    )
    (net (code "110") (name "unconnected-(IC8B-PC4-Pad44)") (class "Default")
      (node (ref "IC8") (pin "44") (pinfunction "PC4_44") (pintype "passive"))
    )
    (net (code "111") (name "unconnected-(IC8B-PE7-Pad58)") (class "Default")
      (node (ref "IC8") (pin "58") (pinfunction "PE7_58") (pintype "passive"))
    )
    (net (code "112") (name "unconnected-(IC8B-PE8-Pad59)") (class "Default")
      (node (ref "IC8") (pin "59") (pinfunction "PE8_59") (pintype "passive"))
    )
    (net (code "113") (name "unconnected-(IC8B-PE10-Pad63)") (class "Default")
      (node (ref "IC8") (pin "63") (pinfunction "PE10_63") (pintype "passive"))
    )
    (net (code "114") (name "unconnected-(IC8B-PE12-Pad65)") (class "Default")
      (node (ref "IC8") (pin "65") (pinfunction "PE12_65") (pintype "passive"))
    )
    (net (code "115") (name "unconnected-(IC8B-PE15-Pad68)") (class "Default")
      (node (ref "IC8") (pin "68") (pinfunction "PE15_68") (pintype "passive"))
    )
    (net (code "116") (name "unconnected-(IC8B-PF11-Pad49)") (class "Default")
      (node (ref "IC8") (pin "49") (pinfunction "PF11_49") (pintype "passive"))
    )
    (net (code "117") (name "unconnected-(IC8B-PF13-Pad53)") (class "Default")
      (node (ref "IC8") (pin "53") (pinfunction "PF13_53") (pintype "passive"))
    )
    (net (code "118") (name "unconnected-(IC8B-PF15-Pad55)") (class "Default")
      (node (ref "IC8") (pin "55") (pinfunction "PF15_55") (pintype "passive"))
    )
    (net (code "119") (name "unconnected-(IC8B-PG0-Pad56)") (class "Default")
      (node (ref "IC8") (pin "56") (pinfunction "PG0_56") (pintype "passive"))
    )
    (net (code "120") (name "unconnected-(IC8B-PG1-Pad57)") (class "Default")
      (node (ref "IC8") (pin "57") (pinfunction "PG1_57") (pintype "passive"))
    )
    (net (code "121") (name "unconnected-(IC8C-PC6-Pad96)") (class "Default")
      (node (ref "IC8") (pin "96") (pinfunction "PC6_96") (pintype "passive"))
    )
    (net (code "122") (name "unconnected-(IC8C-PD10-Pad79)") (class "Default")
      (node (ref "IC8") (pin "79") (pinfunction "PD10_79") (pintype "passive"))
    )
    (net (code "123") (name "unconnected-(IC8C-PD11-Pad80)") (class "Default")
      (node (ref "IC8") (pin "80") (pinfunction "PD11_80") (pintype "passive"))
    )
    (net (code "124") (name "unconnected-(IC8C-PD14-Pad85)") (class "Default")
      (node (ref "IC8") (pin "85") (pinfunction "PD14_85") (pintype "passive"))
    )
    (net (code "125") (name "unconnected-(IC8C-PD15-Pad86)") (class "Default")
      (node (ref "IC8") (pin "86") (pinfunction "PD15_86") (pintype "passive"))
    )
    (net (code "126") (name "unconnected-(IC8C-PG2-Pad87)") (class "Default")
      (node (ref "IC8") (pin "87") (pinfunction "PG2_87") (pintype "passive"))
    )
    (net (code "127") (name "unconnected-(IC8C-PG3-Pad88)") (class "Default")
      (node (ref "IC8") (pin "88") (pinfunction "PG3_88") (pintype "passive"))
    )
    (net (code "128") (name "unconnected-(IC8C-PG4-Pad89)") (class "Default")
      (node (ref "IC8") (pin "89") (pinfunction "PG4_89") (pintype "passive"))
    )
    (net (code "129") (name "unconnected-(IC8C-PG5-Pad90)") (class "Default")
      (node (ref "IC8") (pin "90") (pinfunction "PG5_90") (pintype "passive"))
    )
    (net (code "130") (name "unconnected-(IC8C-PG8-Pad93)") (class "Default")
      (node (ref "IC8") (pin "93") (pinfunction "PG8_93") (pintype "passive"))
    )
    (net (code "131") (name "unconnected-(IC8D-PB4-Pad134)") (class "Default")
      (node (ref "IC8") (pin "134") (pinfunction "PB4_134") (pintype "passive"))
    )
    (net (code "132") (name "unconnected-(IC8D-PB5-Pad135)") (class "Default")
      (node (ref "IC8") (pin "135") (pinfunction "PB5_135") (pintype "passive"))
    )
    (net (code "133") (name "unconnected-(IC8D-PB8-Pad139)") (class "Default")
      (node (ref "IC8") (pin "139") (pinfunction "PB8_139") (pintype "passive"))
    )
    (net (code "134") (name "unconnected-(IC8D-PD6-Pad122)") (class "Default")
      (node (ref "IC8") (pin "122") (pinfunction "PD6_122") (pintype "passive"))
    )
    (net (code "135") (name "unconnected-(IC8D-PD7-Pad123)") (class "Default")
      (node (ref "IC8") (pin "123") (pinfunction "PD7_123") (pintype "passive"))
    )
    (net (code "136") (name "unconnected-(IC8D-PE0-Pad141)") (class "Default")
      (node (ref "IC8") (pin "141") (pinfunction "PE0_141") (pintype "passive"))
    )
    (net (code "137") (name "unconnected-(IC8D-PE1-Pad142)") (class "Default")
      (node (ref "IC8") (pin "142") (pinfunction "PE1_142") (pintype "passive"))
    )
    (net (code "138") (name "unconnected-(IC8D-PG10-Pad125)") (class "Default")
      (node (ref "IC8") (pin "125") (pinfunction "PG10_125") (pintype "passive"))
    )
    (net (code "139") (name "unconnected-(IC8D-PG11-Pad126)") (class "Default")
      (node (ref "IC8") (pin "126") (pinfunction "PG11_126") (pintype "passive"))
    )
    (net (code "140") (name "unconnected-(IC8D-PG12-Pad127)") (class "Default")
      (node (ref "IC8") (pin "127") (pinfunction "PG12_127") (pintype "passive"))
    )
    (net (code "141") (name "unconnected-(IC8D-PG13-Pad128)") (class "Default")
      (node (ref "IC8") (pin "128") (pinfunction "PG13_128") (pintype "passive"))
    )
    (net (code "142") (name "unconnected-(IC8D-PG14-Pad129)") (class "Default")
      (node (ref "IC8") (pin "129") (pinfunction "PG14_129") (pintype "passive"))
    )
    (net (code "143") (name "unconnected-(IC8D-PG15-Pad132)") (class "Default")
      (node (ref "IC8") (pin "132") (pinfunction "PG15_132") (pintype "passive"))
    )
  )
)
